# Solenoise_v4.net
KiCad netlist of a schematic drawn in EAGLE
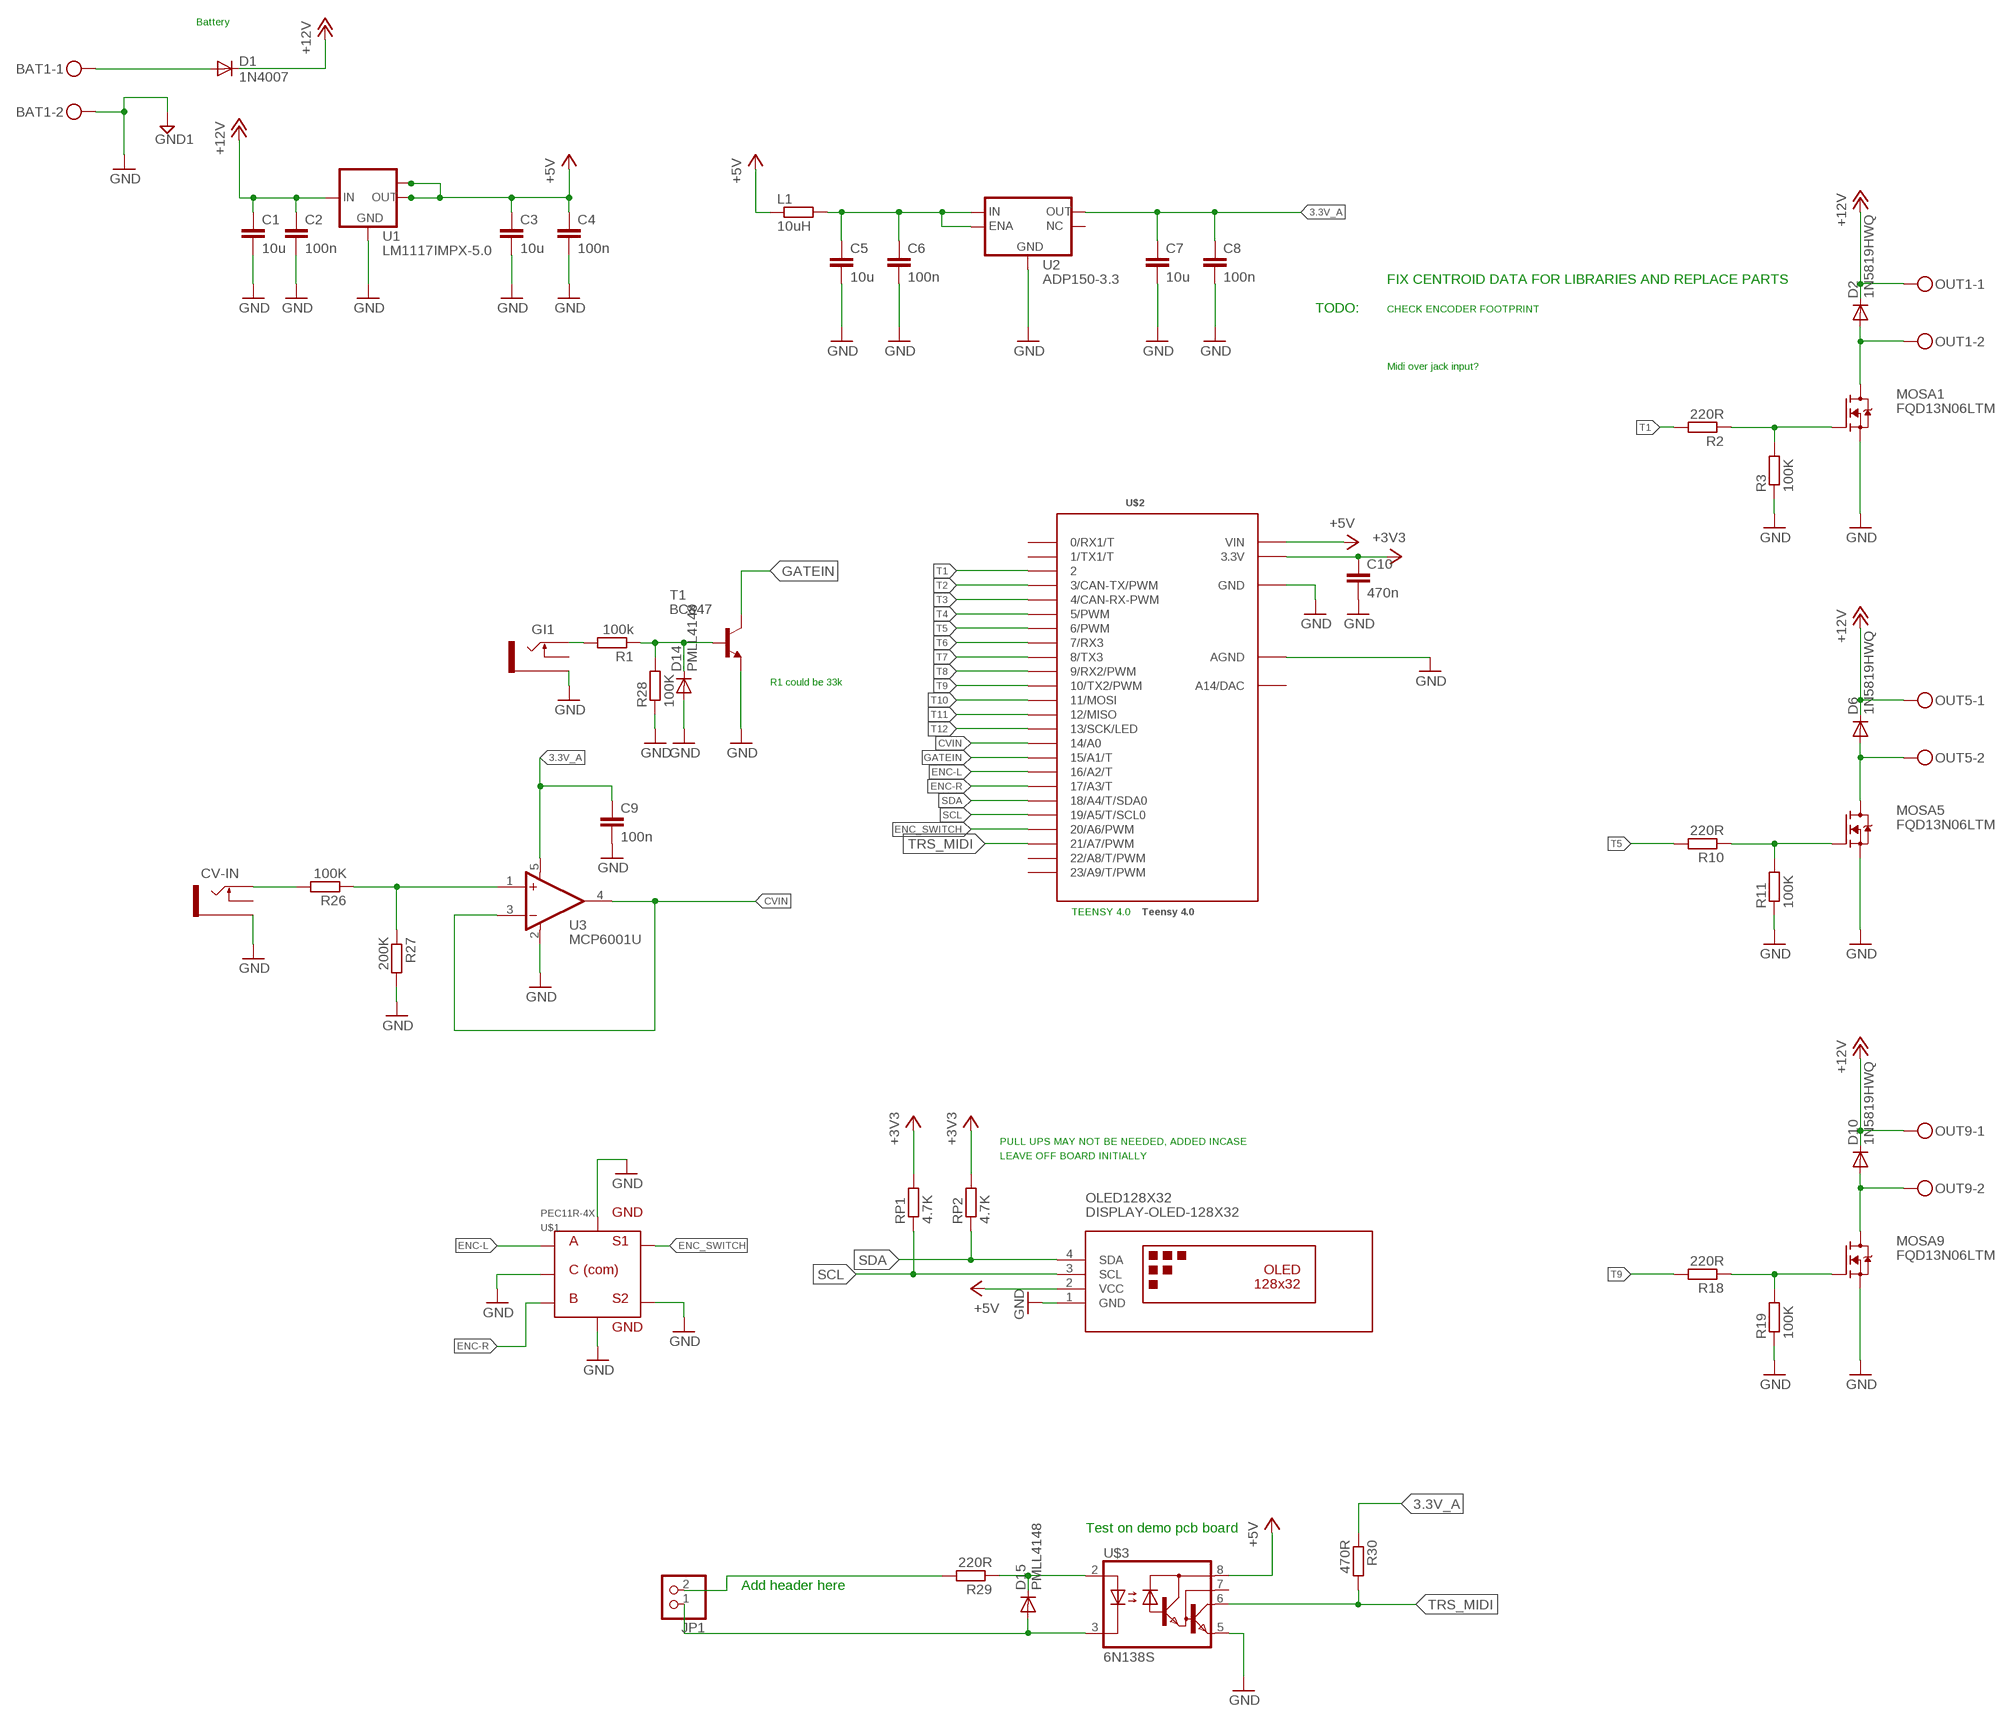
[diagram p0: schematic, sheet 1, part 1 of 2]
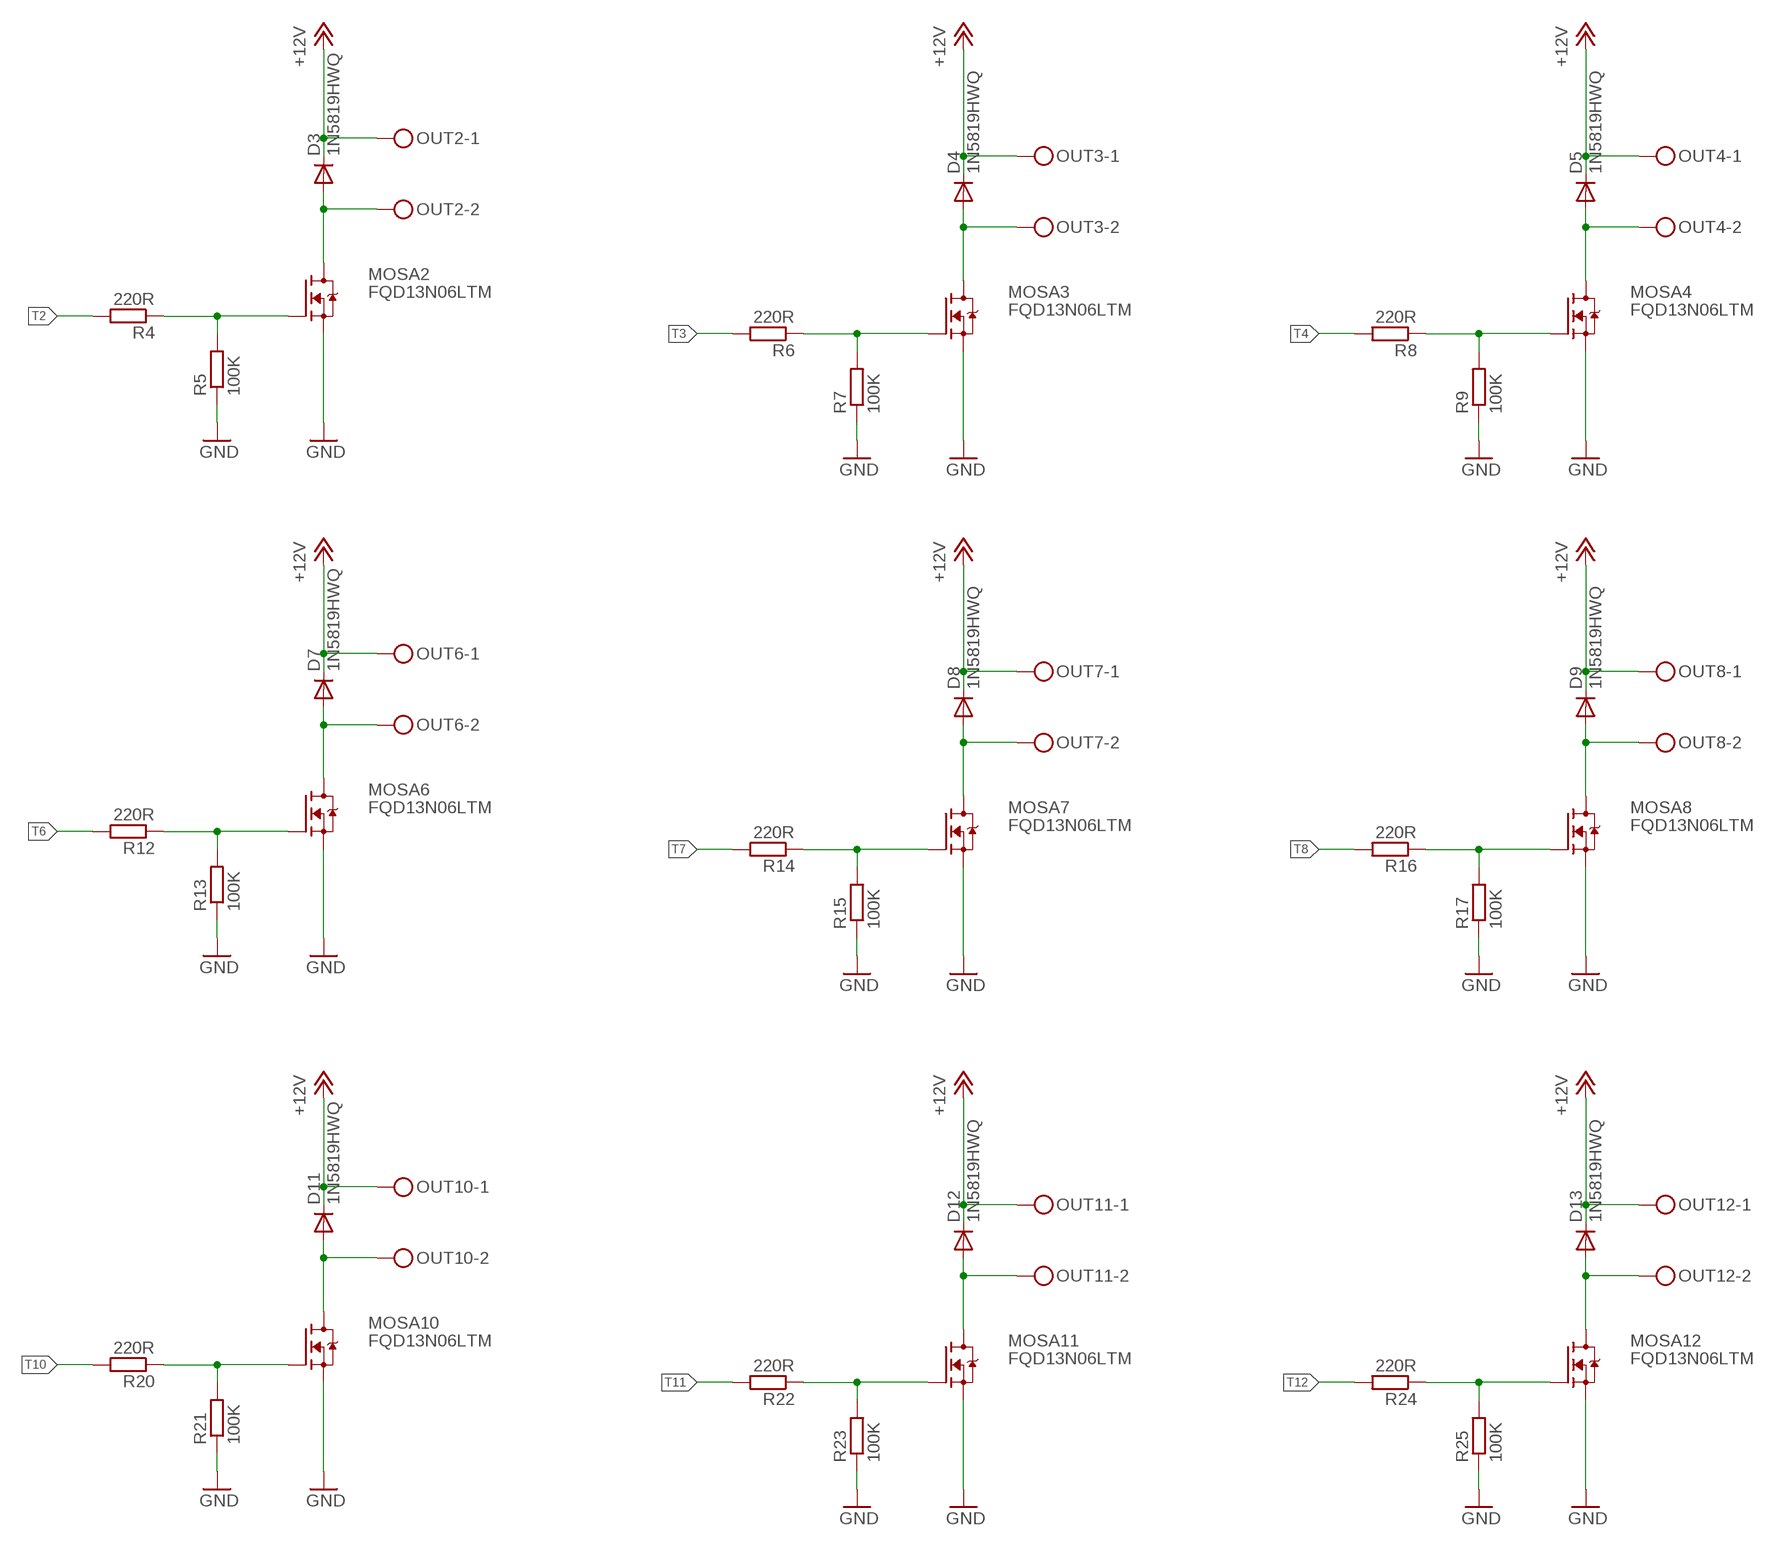
[diagram p1: schematic, sheet 1, part 2 of 2]

(export (version "E")
  (design (tool "Eeschema 10.0.6"))
  (components
    (comp (ref "BAT1")
      (value "MKDSN1,5/2-5,08")
      (footprint "eagle-import:MKDSN1,5_2-5,08")
      (fields (field (name "MPN") "MKDSN 1,5/2-5.08"))
      (libsource (lib "eagle-import") (part "MKDSN1,5/2-5,08"))
    )
    (comp (ref "C1")
      (value "10u")
      (footprint "eagle-import:C1206")
      (libsource (lib "eagle-import") (part "C-EUC1206"))
    )
    (comp (ref "C2")
      (value "100n")
      (footprint "eagle-import:C0805")
      (libsource (lib "eagle-import") (part "C-EUC0805"))
    )
    (comp (ref "C3")
      (value "10u")
      (footprint "eagle-import:C1206")
      (libsource (lib "eagle-import") (part "C-EUC1206"))
    )
    (comp (ref "C4")
      (value "100n")
      (footprint "eagle-import:C0805")
      (libsource (lib "eagle-import") (part "C-EUC0805"))
    )
    (comp (ref "C5")
      (value "10u")
      (footprint "eagle-import:C1206")
      (libsource (lib "eagle-import") (part "C-EUC1206"))
    )
    (comp (ref "C6")
      (value "100n")
      (footprint "eagle-import:C0805")
      (libsource (lib "eagle-import") (part "C-EUC0805"))
    )
    (comp (ref "C7")
      (value "10u")
      (footprint "eagle-import:C1206")
      (libsource (lib "eagle-import") (part "C-EUC1206"))
    )
    (comp (ref "C8")
      (value "100n")
      (footprint "eagle-import:C0805")
      (libsource (lib "eagle-import") (part "C-EUC0805"))
    )
    (comp (ref "C9")
      (value "100n")
      (footprint "eagle-import:C0805")
      (libsource (lib "eagle-import") (part "C-EUC0805"))
    )
    (comp (ref "C10")
      (value "470n")
      (footprint "eagle-import:C0805")
      (libsource (lib "eagle-import") (part "C-EUC0805"))
    )
    (comp (ref "CV-IN")
      (value "THONKICONNNEW")
      (footprint "eagle-import:WQP-PJ301M-12_JACK")
      (libsource (lib "eagle-import") (part "THONKICONNNEW"))
    )
    (comp (ref "D1")
      (value "1N4007")
      (footprint "eagle-import:DO41-10")
      (libsource (lib "eagle-import") (part "1N4004"))
    )
    (comp (ref "D2")
      (value "1N5819HWQ")
      (footprint "eagle-import:SOD123")
      (libsource (lib "eagle-import") (part "MBR0520LT"))
    )
    (comp (ref "D3")
      (value "1N5819HWQ")
      (footprint "eagle-import:SOD123")
      (libsource (lib "eagle-import") (part "MBR0520LT"))
    )
    (comp (ref "D4")
      (value "1N5819HWQ")
      (footprint "eagle-import:SOD123")
      (libsource (lib "eagle-import") (part "MBR0520LT"))
    )
    (comp (ref "D5")
      (value "1N5819HWQ")
      (footprint "eagle-import:SOD123")
      (libsource (lib "eagle-import") (part "MBR0520LT"))
    )
    (comp (ref "D6")
      (value "1N5819HWQ")
      (footprint "eagle-import:SOD123")
      (libsource (lib "eagle-import") (part "MBR0520LT"))
    )
    (comp (ref "D7")
      (value "1N5819HWQ")
      (footprint "eagle-import:SOD123")
      (libsource (lib "eagle-import") (part "MBR0520LT"))
    )
    (comp (ref "D8")
      (value "1N5819HWQ")
      (footprint "eagle-import:SOD123")
      (libsource (lib "eagle-import") (part "MBR0520LT"))
    )
    (comp (ref "D9")
      (value "1N5819HWQ")
      (footprint "eagle-import:SOD123")
      (libsource (lib "eagle-import") (part "MBR0520LT"))
    )
    (comp (ref "D10")
      (value "1N5819HWQ")
      (footprint "eagle-import:SOD123")
      (libsource (lib "eagle-import") (part "MBR0520LT"))
    )
    (comp (ref "D11")
      (value "1N5819HWQ")
      (footprint "eagle-import:SOD123")
      (libsource (lib "eagle-import") (part "MBR0520LT"))
    )
    (comp (ref "D12")
      (value "1N5819HWQ")
      (footprint "eagle-import:SOD123")
      (libsource (lib "eagle-import") (part "MBR0520LT"))
    )
    (comp (ref "D13")
      (value "1N5819HWQ")
      (footprint "eagle-import:SOD123")
      (libsource (lib "eagle-import") (part "MBR0520LT"))
    )
    (comp (ref "D14")
      (value "PMLL4148")
      (footprint "eagle-import:SOD80C")
      (libsource (lib "eagle-import") (part "PMLL4150"))
    )
    (comp (ref "D15")
      (value "PMLL4148")
      (footprint "eagle-import:SOD80C")
      (libsource (lib "eagle-import") (part "PMLL4150"))
    )
    (comp (ref "GI1")
      (value "THONKICONNNEW")
      (footprint "eagle-import:WQP-PJ301M-12_JACK")
      (libsource (lib "eagle-import") (part "THONKICONNNEW"))
    )
    (comp (ref "JP1")
      (value "PINHD-1X2")
      (footprint "eagle-import:1X02")
      (libsource (lib "eagle-import") (part "PINHD-1X2"))
    )
    (comp (ref "L1")
      (value "10uH")
      (footprint "eagle-import:R0805")
      (libsource (lib "eagle-import") (part "R-EU_R0805"))
    )
    (comp (ref "MOSA1")
      (value "FQD13N06LTM")
      (footprint "eagle-import:FQD13N06LTM")
      (libsource (lib "eagle-import") (part "FQD13N06LTM"))
    )
    (comp (ref "MOSA2")
      (value "FQD13N06LTM")
      (footprint "eagle-import:FQD13N06LTM")
      (libsource (lib "eagle-import") (part "FQD13N06LTM"))
    )
    (comp (ref "MOSA3")
      (value "FQD13N06LTM")
      (footprint "eagle-import:FQD13N06LTM")
      (libsource (lib "eagle-import") (part "FQD13N06LTM"))
    )
    (comp (ref "MOSA4")
      (value "FQD13N06LTM")
      (footprint "eagle-import:FQD13N06LTM")
      (libsource (lib "eagle-import") (part "FQD13N06LTM"))
    )
    (comp (ref "MOSA5")
      (value "FQD13N06LTM")
      (footprint "eagle-import:FQD13N06LTM")
      (libsource (lib "eagle-import") (part "FQD13N06LTM"))
    )
    (comp (ref "MOSA6")
      (value "FQD13N06LTM")
      (footprint "eagle-import:FQD13N06LTM")
      (libsource (lib "eagle-import") (part "FQD13N06LTM"))
    )
    (comp (ref "MOSA7")
      (value "FQD13N06LTM")
      (footprint "eagle-import:FQD13N06LTM")
      (libsource (lib "eagle-import") (part "FQD13N06LTM"))
    )
    (comp (ref "MOSA8")
      (value "FQD13N06LTM")
      (footprint "eagle-import:FQD13N06LTM")
      (libsource (lib "eagle-import") (part "FQD13N06LTM"))
    )
    (comp (ref "MOSA9")
      (value "FQD13N06LTM")
      (footprint "eagle-import:FQD13N06LTM")
      (libsource (lib "eagle-import") (part "FQD13N06LTM"))
    )
    (comp (ref "MOSA10")
      (value "FQD13N06LTM")
      (footprint "eagle-import:FQD13N06LTM")
      (libsource (lib "eagle-import") (part "FQD13N06LTM"))
    )
    (comp (ref "MOSA11")
      (value "FQD13N06LTM")
      (footprint "eagle-import:FQD13N06LTM")
      (libsource (lib "eagle-import") (part "FQD13N06LTM"))
    )
    (comp (ref "MOSA12")
      (value "FQD13N06LTM")
      (footprint "eagle-import:FQD13N06LTM")
      (libsource (lib "eagle-import") (part "FQD13N06LTM"))
    )
    (comp (ref "OLED128X32")
      (value "DISPLAY-OLED-128X32")
      (footprint "eagle-import:DISPLAY-OLED-128X32")
      (libsource (lib "eagle-import") (part "DISPLAY-OLED-128X32"))
    )
    (comp (ref "OUT1")
      (value "MKDSN1,5/2-5,08")
      (footprint "eagle-import:MKDSN1,5_2-5,08")
      (fields (field (name "MPN") "MKDSN 1,5/2-5.08"))
      (libsource (lib "eagle-import") (part "MKDSN1,5/2-5,08"))
    )
    (comp (ref "OUT2")
      (value "MKDSN1,5/2-5,08")
      (footprint "eagle-import:MKDSN1,5_2-5,08")
      (fields (field (name "MPN") "MKDSN 1,5/2-5.08"))
      (libsource (lib "eagle-import") (part "MKDSN1,5/2-5,08"))
    )
    (comp (ref "OUT3")
      (value "MKDSN1,5/2-5,08")
      (footprint "eagle-import:MKDSN1,5_2-5,08")
      (fields (field (name "MPN") "MKDSN 1,5/2-5.08"))
      (libsource (lib "eagle-import") (part "MKDSN1,5/2-5,08"))
    )
    (comp (ref "OUT4")
      (value "MKDSN1,5/2-5,08")
      (footprint "eagle-import:MKDSN1,5_2-5,08")
      (fields (field (name "MPN") "MKDSN 1,5/2-5.08"))
      (libsource (lib "eagle-import") (part "MKDSN1,5/2-5,08"))
    )
    (comp (ref "OUT5")
      (value "MKDSN1,5/2-5,08")
      (footprint "eagle-import:MKDSN1,5_2-5,08")
      (fields (field (name "MPN") "MKDSN 1,5/2-5.08"))
      (libsource (lib "eagle-import") (part "MKDSN1,5/2-5,08"))
    )
    (comp (ref "OUT6")
      (value "MKDSN1,5/2-5,08")
      (footprint "eagle-import:MKDSN1,5_2-5,08")
      (fields (field (name "MPN") "MKDSN 1,5/2-5.08"))
      (libsource (lib "eagle-import") (part "MKDSN1,5/2-5,08"))
    )
    (comp (ref "OUT7")
      (value "MKDSN1,5/2-5,08")
      (footprint "eagle-import:MKDSN1,5_2-5,08")
      (fields (field (name "MPN") "MKDSN 1,5/2-5.08"))
      (libsource (lib "eagle-import") (part "MKDSN1,5/2-5,08"))
    )
    (comp (ref "OUT8")
      (value "MKDSN1,5/2-5,08")
      (footprint "eagle-import:MKDSN1,5_2-5,08")
      (fields (field (name "MPN") "MKDSN 1,5/2-5.08"))
      (libsource (lib "eagle-import") (part "MKDSN1,5/2-5,08"))
    )
    (comp (ref "OUT9")
      (value "MKDSN1,5/2-5,08")
      (footprint "eagle-import:MKDSN1,5_2-5,08")
      (fields (field (name "MPN") "MKDSN 1,5/2-5.08"))
      (libsource (lib "eagle-import") (part "MKDSN1,5/2-5,08"))
    )
    (comp (ref "OUT10")
      (value "MKDSN1,5/2-5,08")
      (footprint "eagle-import:MKDSN1,5_2-5,08")
      (fields (field (name "MPN") "MKDSN 1,5/2-5.08"))
      (libsource (lib "eagle-import") (part "MKDSN1,5/2-5,08"))
    )
    (comp (ref "OUT11")
      (value "MKDSN1,5/2-5,08")
      (footprint "eagle-import:MKDSN1,5_2-5,08")
      (fields (field (name "MPN") "MKDSN 1,5/2-5.08"))
      (libsource (lib "eagle-import") (part "MKDSN1,5/2-5,08"))
    )
    (comp (ref "OUT12")
      (value "MKDSN1,5/2-5,08")
      (footprint "eagle-import:MKDSN1,5_2-5,08")
      (fields (field (name "MPN") "MKDSN 1,5/2-5.08"))
      (libsource (lib "eagle-import") (part "MKDSN1,5/2-5,08"))
    )
    (comp (ref "R1")
      (value "100k")
      (footprint "eagle-import:R0805")
      (libsource (lib "eagle-import") (part "R-EU_R0805"))
    )
    (comp (ref "R2")
      (value "220R")
      (footprint "eagle-import:R0805")
      (libsource (lib "eagle-import") (part "R-EU_R0805"))
    )
    (comp (ref "R3")
      (value "100K")
      (footprint "eagle-import:R0805")
      (libsource (lib "eagle-import") (part "R-EU_R0805"))
    )
    (comp (ref "R4")
      (value "220R")
      (footprint "eagle-import:R0805")
      (libsource (lib "eagle-import") (part "R-EU_R0805"))
    )
    (comp (ref "R5")
      (value "100K")
      (footprint "eagle-import:R0805")
      (libsource (lib "eagle-import") (part "R-EU_R0805"))
    )
    (comp (ref "R6")
      (value "220R")
      (footprint "eagle-import:R0805")
      (libsource (lib "eagle-import") (part "R-EU_R0805"))
    )
    (comp (ref "R7")
      (value "100K")
      (footprint "eagle-import:R0805")
      (libsource (lib "eagle-import") (part "R-EU_R0805"))
    )
    (comp (ref "R8")
      (value "220R")
      (footprint "eagle-import:R0805")
      (libsource (lib "eagle-import") (part "R-EU_R0805"))
    )
    (comp (ref "R9")
      (value "100K")
      (footprint "eagle-import:R0805")
      (libsource (lib "eagle-import") (part "R-EU_R0805"))
    )
    (comp (ref "R10")
      (value "220R")
      (footprint "eagle-import:R0805")
      (libsource (lib "eagle-import") (part "R-EU_R0805"))
    )
    (comp (ref "R11")
      (value "100K")
      (footprint "eagle-import:R0805")
      (libsource (lib "eagle-import") (part "R-EU_R0805"))
    )
    (comp (ref "R12")
      (value "220R")
      (footprint "eagle-import:R0805")
      (libsource (lib "eagle-import") (part "R-EU_R0805"))
    )
    (comp (ref "R13")
      (value "100K")
      (footprint "eagle-import:R0805")
      (libsource (lib "eagle-import") (part "R-EU_R0805"))
    )
    (comp (ref "R14")
      (value "220R")
      (footprint "eagle-import:R0805")
      (libsource (lib "eagle-import") (part "R-EU_R0805"))
    )
    (comp (ref "R15")
      (value "100K")
      (footprint "eagle-import:R0805")
      (libsource (lib "eagle-import") (part "R-EU_R0805"))
    )
    (comp (ref "R16")
      (value "220R")
      (footprint "eagle-import:R0805")
      (libsource (lib "eagle-import") (part "R-EU_R0805"))
    )
    (comp (ref "R17")
      (value "100K")
      (footprint "eagle-import:R0805")
      (libsource (lib "eagle-import") (part "R-EU_R0805"))
    )
    (comp (ref "R18")
      (value "220R")
      (footprint "eagle-import:R0805")
      (libsource (lib "eagle-import") (part "R-EU_R0805"))
    )
    (comp (ref "R19")
      (value "100K")
      (footprint "eagle-import:R0805")
      (libsource (lib "eagle-import") (part "R-EU_R0805"))
    )
    (comp (ref "R20")
      (value "220R")
      (footprint "eagle-import:R0805")
      (libsource (lib "eagle-import") (part "R-EU_R0805"))
    )
    (comp (ref "R21")
      (value "100K")
      (footprint "eagle-import:R0805")
      (libsource (lib "eagle-import") (part "R-EU_R0805"))
    )
    (comp (ref "R22")
      (value "220R")
      (footprint "eagle-import:R0805")
      (libsource (lib "eagle-import") (part "R-EU_R0805"))
    )
    (comp (ref "R23")
      (value "100K")
      (footprint "eagle-import:R0805")
      (libsource (lib "eagle-import") (part "R-EU_R0805"))
    )
    (comp (ref "R24")
      (value "220R")
      (footprint "eagle-import:R0805")
      (libsource (lib "eagle-import") (part "R-EU_R0805"))
    )
    (comp (ref "R25")
      (value "100K")
      (footprint "eagle-import:R0805")
      (libsource (lib "eagle-import") (part "R-EU_R0805"))
    )
    (comp (ref "R26")
      (value "100K")
      (footprint "eagle-import:R0805")
      (libsource (lib "eagle-import") (part "R-EU_R0805"))
    )
    (comp (ref "R27")
      (value "200K")
      (footprint "eagle-import:R0805")
      (libsource (lib "eagle-import") (part "R-EU_R0805"))
    )
    (comp (ref "R28")
      (value "100K")
      (footprint "eagle-import:R0805")
      (libsource (lib "eagle-import") (part "R-EU_R0805"))
    )
    (comp (ref "R29")
      (value "220R")
      (footprint "eagle-import:R0805")
      (libsource (lib "eagle-import") (part "R-EU_R0805"))
    )
    (comp (ref "R30")
      (value "470R")
      (footprint "eagle-import:R0805")
      (libsource (lib "eagle-import") (part "R-EU_R0805"))
    )
    (comp (ref "RP1")
      (value "4.7K")
      (footprint "eagle-import:R0805")
      (libsource (lib "eagle-import") (part "R-EU_R0805"))
    )
    (comp (ref "RP2")
      (value "4.7K")
      (footprint "eagle-import:R0805")
      (libsource (lib "eagle-import") (part "R-EU_R0805"))
    )
    (comp (ref "T1")
      (value "BC847")
      (footprint "eagle-import:SOT23")
      (libsource (lib "eagle-import") (part "BC847"))
    )
    (comp (ref "U$1")
      (value "PEC11R-4X")
      (footprint "eagle-import:ENC")
      (libsource (lib "eagle-import") (part "PEC11R-4X"))
    )
    (comp (ref "U$2")
      (value "Teensy 4.0")
      (footprint "eagle-import:TEENSY_3.1_DAC")
      (libsource (lib "eagle-import") (part "TEENSY_3.1_DAC"))
    )
    (comp (ref "U$3")
      (value "6N138S")
      (footprint "eagle-import:6N138S")
      (libsource (lib "eagle-import") (part "6N138S"))
    )
    (comp (ref "U1")
      (value "LM1117IMPX-5.0")
      (footprint "eagle-import:SOT223")
      (libsource (lib "eagle-import") (part "LM1117IMPX-5.0"))
    )
    (comp (ref "U2")
      (value "ADP150-3.3")
      (footprint "eagle-import:SOT23-5")
      (libsource (lib "eagle-import") (part "ADP150-3.3"))
    )
    (comp (ref "U3")
      (value "MCP6001U")
      (footprint "eagle-import:MCP6001")
      (libsource (lib "eagle-import") (part "MCP6001U"))
    )
  )
  (nets
    (net (code "1") (name "+3V3") (class "Default")
      (node (ref "C10") (pin "1") (pinfunction "1_1") (pintype "passive"))
      (node (ref "RP1") (pin "2") (pinfunction "2_2") (pintype "passive"))
      (node (ref "RP2") (pin "2") (pinfunction "2_2") (pintype "passive"))
      (node (ref "U$2") (pin "3.3V") (pinfunction "3.3V_3.3V") (pintype "power_in"))
    )
    (net (code "2") (name "+5V") (class "Default")
      (node (ref "C3") (pin "1") (pinfunction "1_1") (pintype "passive"))
      (node (ref "C4") (pin "1") (pinfunction "1_1") (pintype "passive"))
      (node (ref "L1") (pin "1") (pinfunction "1_1") (pintype "passive"))
      (node (ref "OLED128X32") (pin "2") (pinfunction "VCC_2") (pintype "power_in"))
      (node (ref "U$2") (pin "VIN") (pinfunction "VIN_VIN") (pintype "power_in"))
      (node (ref "U$3") (pin "8") (pinfunction "VCC_8") (pintype "passive"))
      (node (ref "U1") (pin "2") (pinfunction "OUT_2") (pintype "passive"))
      (node (ref "U1") (pin "TAB") (pinfunction "OUT1_TAB") (pintype "passive"))
    )
    (net (code "3") (name "+12V") (class "Default")
      (node (ref "C1") (pin "1") (pinfunction "1_1") (pintype "passive"))
      (node (ref "C2") (pin "1") (pinfunction "1_1") (pintype "passive"))
      (node (ref "D1") (pin "C") (pinfunction "C_C") (pintype "passive"))
      (node (ref "D10") (pin "C") (pinfunction "C_C") (pintype "passive"))
      (node (ref "D11") (pin "C") (pinfunction "C_C") (pintype "passive"))
      (node (ref "D12") (pin "C") (pinfunction "C_C") (pintype "passive"))
      (node (ref "D13") (pin "C") (pinfunction "C_C") (pintype "passive"))
      (node (ref "D2") (pin "C") (pinfunction "C_C") (pintype "passive"))
      (node (ref "D3") (pin "C") (pinfunction "C_C") (pintype "passive"))
      (node (ref "D4") (pin "C") (pinfunction "C_C") (pintype "passive"))
      (node (ref "D5") (pin "C") (pinfunction "C_C") (pintype "passive"))
      (node (ref "D6") (pin "C") (pinfunction "C_C") (pintype "passive"))
      (node (ref "D7") (pin "C") (pinfunction "C_C") (pintype "passive"))
      (node (ref "D8") (pin "C") (pinfunction "C_C") (pintype "passive"))
      (node (ref "D9") (pin "C") (pinfunction "C_C") (pintype "passive"))
      (node (ref "OUT1") (pin "1") (pinfunction "KL_1") (pintype "passive"))
      (node (ref "OUT10") (pin "1") (pinfunction "KL_1") (pintype "passive"))
      (node (ref "OUT11") (pin "1") (pinfunction "KL_1") (pintype "passive"))
      (node (ref "OUT12") (pin "1") (pinfunction "KL_1") (pintype "passive"))
      (node (ref "OUT2") (pin "1") (pinfunction "KL_1") (pintype "passive"))
      (node (ref "OUT3") (pin "1") (pinfunction "KL_1") (pintype "passive"))
      (node (ref "OUT4") (pin "1") (pinfunction "KL_1") (pintype "passive"))
      (node (ref "OUT5") (pin "1") (pinfunction "KL_1") (pintype "passive"))
      (node (ref "OUT6") (pin "1") (pinfunction "KL_1") (pintype "passive"))
      (node (ref "OUT7") (pin "1") (pinfunction "KL_1") (pintype "passive"))
      (node (ref "OUT8") (pin "1") (pinfunction "KL_1") (pintype "passive"))
      (node (ref "OUT9") (pin "1") (pinfunction "KL_1") (pintype "passive"))
      (node (ref "U1") (pin "3") (pinfunction "IN_3") (pintype "input"))
    )
    (net (code "4") (name "3.3V_A") (class "Default")
      (node (ref "C7") (pin "1") (pinfunction "1_1") (pintype "passive"))
      (node (ref "C8") (pin "1") (pinfunction "1_1") (pintype "passive"))
      (node (ref "C9") (pin "1") (pinfunction "1_1") (pintype "passive"))
      (node (ref "R30") (pin "1") (pinfunction "1_1") (pintype "passive"))
      (node (ref "U2") (pin "OUT") (pinfunction "VOUT_OUT") (pintype "passive"))
      (node (ref "U3") (pin "5") (pinfunction "V+_5") (pintype "power_in"))
    )
    (net (code "5") (name "CVIN") (class "Default")
      (node (ref "U$2") (pin "14/A0") (pinfunction "14/A0_14/A0") (pintype "bidirectional"))
      (node (ref "U3") (pin "3") (pinfunction "-IN_3") (pintype "input"))
      (node (ref "U3") (pin "4") (pinfunction "OUT_4") (pintype "output"))
    )
    (net (code "6") (name "ENC-L") (class "Default")
      (node (ref "U$1") (pin "A") (pinfunction "A_A") (pintype "passive"))
      (node (ref "U$2") (pin "16/A2") (pinfunction "16/A2/T_16/A2") (pintype "bidirectional"))
    )
    (net (code "7") (name "ENC-R") (class "Default")
      (node (ref "U$1") (pin "B") (pinfunction "B_B") (pintype "passive"))
      (node (ref "U$2") (pin "17/A3") (pinfunction "17/A3/T_17/A3") (pintype "bidirectional"))
    )
    (net (code "8") (name "ENC_SWITCH") (class "Default")
      (node (ref "U$1") (pin "1") (pinfunction "SW1_1") (pintype "passive"))
      (node (ref "U$2") (pin "20/A6") (pinfunction "20/A6/PWM_20/A6") (pintype "bidirectional"))
    )
    (net (code "9") (name "GATEIN") (class "Default")
      (node (ref "T1") (pin "3") (pinfunction "C_3") (pintype "passive"))
      (node (ref "U$2") (pin "15/A1") (pinfunction "15/A1/T_15/A1") (pintype "bidirectional"))
    )
    (net (code "10") (name "GND") (class "Default")
      (node (ref "BAT1") (pin "2") (pinfunction "KL_2") (pintype "passive"))
      (node (ref "C1") (pin "2") (pinfunction "2_2") (pintype "passive"))
      (node (ref "C10") (pin "2") (pinfunction "2_2") (pintype "passive"))
      (node (ref "C2") (pin "2") (pinfunction "2_2") (pintype "passive"))
      (node (ref "C3") (pin "2") (pinfunction "2_2") (pintype "passive"))
      (node (ref "C4") (pin "2") (pinfunction "2_2") (pintype "passive"))
      (node (ref "C5") (pin "2") (pinfunction "2_2") (pintype "passive"))
      (node (ref "C6") (pin "2") (pinfunction "2_2") (pintype "passive"))
      (node (ref "C7") (pin "2") (pinfunction "2_2") (pintype "passive"))
      (node (ref "C8") (pin "2") (pinfunction "2_2") (pintype "passive"))
      (node (ref "C9") (pin "2") (pinfunction "2_2") (pintype "passive"))
      (node (ref "CV-IN") (pin "P$3_SLEEVE") (pinfunction "SLEEVE_P$3_SLEEVE") (pintype "passive"))
      (node (ref "D14") (pin "A") (pinfunction "A_A") (pintype "passive"))
      (node (ref "GI1") (pin "P$3_SLEEVE") (pinfunction "SLEEVE_P$3_SLEEVE") (pintype "passive"))
      (node (ref "MOSA1") (pin "2") (pinfunction "S_2") (pintype "passive"))
      (node (ref "MOSA10") (pin "2") (pinfunction "S_2") (pintype "passive"))
      (node (ref "MOSA11") (pin "2") (pinfunction "S_2") (pintype "passive"))
      (node (ref "MOSA12") (pin "2") (pinfunction "S_2") (pintype "passive"))
      (node (ref "MOSA2") (pin "2") (pinfunction "S_2") (pintype "passive"))
      (node (ref "MOSA3") (pin "2") (pinfunction "S_2") (pintype "passive"))
      (node (ref "MOSA4") (pin "2") (pinfunction "S_2") (pintype "passive"))
      (node (ref "MOSA5") (pin "2") (pinfunction "S_2") (pintype "passive"))
      (node (ref "MOSA6") (pin "2") (pinfunction "S_2") (pintype "passive"))
      (node (ref "MOSA7") (pin "2") (pinfunction "S_2") (pintype "passive"))
      (node (ref "MOSA8") (pin "2") (pinfunction "S_2") (pintype "passive"))
      (node (ref "MOSA9") (pin "2") (pinfunction "S_2") (pintype "passive"))
      (node (ref "OLED128X32") (pin "1") (pinfunction "GND_1") (pintype "power_in"))
      (node (ref "R11") (pin "1") (pinfunction "1_1") (pintype "passive"))
      (node (ref "R13") (pin "1") (pinfunction "1_1") (pintype "passive"))
      (node (ref "R15") (pin "1") (pinfunction "1_1") (pintype "passive"))
      (node (ref "R17") (pin "1") (pinfunction "1_1") (pintype "passive"))
      (node (ref "R19") (pin "1") (pinfunction "1_1") (pintype "passive"))
      (node (ref "R21") (pin "1") (pinfunction "1_1") (pintype "passive"))
      (node (ref "R23") (pin "1") (pinfunction "1_1") (pintype "passive"))
      (node (ref "R25") (pin "1") (pinfunction "1_1") (pintype "passive"))
      (node (ref "R27") (pin "2") (pinfunction "2_2") (pintype "passive"))
      (node (ref "R28") (pin "1") (pinfunction "1_1") (pintype "passive"))
      (node (ref "R3") (pin "1") (pinfunction "1_1") (pintype "passive"))
      (node (ref "R5") (pin "1") (pinfunction "1_1") (pintype "passive"))
      (node (ref "R7") (pin "1") (pinfunction "1_1") (pintype "passive"))
      (node (ref "R9") (pin "1") (pinfunction "1_1") (pintype "passive"))
      (node (ref "T1") (pin "2") (pinfunction "E_2") (pintype "passive"))
      (node (ref "U$1") (pin "2") (pinfunction "SW2_2") (pintype "passive"))
      (node (ref "U$1") (pin "C") (pinfunction "C_C") (pintype "passive"))
      (node (ref "U$1") (pin "GND1") (pinfunction "GND1_GND1") (pintype "passive"))
      (node (ref "U$1") (pin "GND2") (pinfunction "GND2_GND2") (pintype "passive"))
      (node (ref "U$2") (pin "AGND") (pinfunction "AGND_AGND") (pintype "power_in"))
      (node (ref "U$2") (pin "GND") (pinfunction "GND_GND") (pintype "power_in"))
      (node (ref "U$3") (pin "5") (pinfunction "GND_5") (pintype "passive"))
      (node (ref "U1") (pin "1") (pinfunction "GND_1") (pintype "input"))
      (node (ref "U2") (pin "GND") (pinfunction "GND_GND") (pintype "input"))
      (node (ref "U3") (pin "2") (pinfunction "V-_2") (pintype "power_in"))
    )
    (net (code "11") (name "Net-(BAT1A-KL)") (class "Default")
      (node (ref "BAT1") (pin "1") (pinfunction "KL_1") (pintype "passive"))
      (node (ref "D1") (pin "A") (pinfunction "A_A") (pintype "passive"))
    )
    (net (code "12") (name "Net-(CV-IN-TIP)") (class "Default")
      (node (ref "CV-IN") (pin "P$1_TIP") (pinfunction "TIP_P$1_TIP") (pintype "passive"))
      (node (ref "R26") (pin "2") (pinfunction "2_2") (pintype "passive"))
    )
    (net (code "13") (name "Net-(GI1-TIP)") (class "Default")
      (node (ref "GI1") (pin "P$1_TIP") (pinfunction "TIP_P$1_TIP") (pintype "passive"))
      (node (ref "R1") (pin "2") (pinfunction "2_2") (pintype "passive"))
    )
    (net (code "14") (name "Net-(JP1-Pad2)") (class "Default")
      (node (ref "JP1") (pin "2") (pinfunction "2_2") (pintype "passive"))
      (node (ref "R29") (pin "2") (pinfunction "2_2") (pintype "passive"))
    )
    (net (code "15") (name "Net-(MOSA1-D)") (class "Default")
      (node (ref "D2") (pin "A") (pinfunction "A_A") (pintype "passive"))
      (node (ref "MOSA1") (pin "3") (pinfunction "D_3") (pintype "passive"))
      (node (ref "OUT1") (pin "2") (pinfunction "KL_2") (pintype "passive"))
    )
    (net (code "16") (name "Net-(MOSA1-G)") (class "Default")
      (node (ref "MOSA1") (pin "1") (pinfunction "G_1") (pintype "passive"))
      (node (ref "R2") (pin "1") (pinfunction "1_1") (pintype "passive"))
      (node (ref "R3") (pin "2") (pinfunction "2_2") (pintype "passive"))
    )
    (net (code "17") (name "Net-(MOSA2-D)") (class "Default")
      (node (ref "D3") (pin "A") (pinfunction "A_A") (pintype "passive"))
      (node (ref "MOSA2") (pin "3") (pinfunction "D_3") (pintype "passive"))
      (node (ref "OUT2") (pin "2") (pinfunction "KL_2") (pintype "passive"))
    )
    (net (code "18") (name "Net-(MOSA2-G)") (class "Default")
      (node (ref "MOSA2") (pin "1") (pinfunction "G_1") (pintype "passive"))
      (node (ref "R4") (pin "1") (pinfunction "1_1") (pintype "passive"))
      (node (ref "R5") (pin "2") (pinfunction "2_2") (pintype "passive"))
    )
    (net (code "19") (name "Net-(MOSA3-D)") (class "Default")
      (node (ref "D4") (pin "A") (pinfunction "A_A") (pintype "passive"))
      (node (ref "MOSA3") (pin "3") (pinfunction "D_3") (pintype "passive"))
      (node (ref "OUT3") (pin "2") (pinfunction "KL_2") (pintype "passive"))
    )
    (net (code "20") (name "Net-(MOSA3-G)") (class "Default")
      (node (ref "MOSA3") (pin "1") (pinfunction "G_1") (pintype "passive"))
      (node (ref "R6") (pin "1") (pinfunction "1_1") (pintype "passive"))
      (node (ref "R7") (pin "2") (pinfunction "2_2") (pintype "passive"))
    )
    (net (code "21") (name "Net-(MOSA4-D)") (class "Default")
      (node (ref "D5") (pin "A") (pinfunction "A_A") (pintype "passive"))
      (node (ref "MOSA4") (pin "3") (pinfunction "D_3") (pintype "passive"))
      (node (ref "OUT4") (pin "2") (pinfunction "KL_2") (pintype "passive"))
    )
    (net (code "22") (name "Net-(MOSA4-G)") (class "Default")
      (node (ref "MOSA4") (pin "1") (pinfunction "G_1") (pintype "passive"))
      (node (ref "R8") (pin "1") (pinfunction "1_1") (pintype "passive"))
      (node (ref "R9") (pin "2") (pinfunction "2_2") (pintype "passive"))
    )
    (net (code "23") (name "Net-(MOSA5-D)") (class "Default")
      (node (ref "D6") (pin "A") (pinfunction "A_A") (pintype "passive"))
      (node (ref "MOSA5") (pin "3") (pinfunction "D_3") (pintype "passive"))
      (node (ref "OUT5") (pin "2") (pinfunction "KL_2") (pintype "passive"))
    )
    (net (code "24") (name "Net-(MOSA5-G)") (class "Default")
      (node (ref "MOSA5") (pin "1") (pinfunction "G_1") (pintype "passive"))
      (node (ref "R10") (pin "1") (pinfunction "1_1") (pintype "passive"))
      (node (ref "R11") (pin "2") (pinfunction "2_2") (pintype "passive"))
    )
    (net (code "25") (name "Net-(MOSA6-D)") (class "Default")
      (node (ref "D7") (pin "A") (pinfunction "A_A") (pintype "passive"))
      (node (ref "MOSA6") (pin "3") (pinfunction "D_3") (pintype "passive"))
      (node (ref "OUT6") (pin "2") (pinfunction "KL_2") (pintype "passive"))
    )
    (net (code "26") (name "Net-(MOSA6-G)") (class "Default")
      (node (ref "MOSA6") (pin "1") (pinfunction "G_1") (pintype "passive"))
      (node (ref "R12") (pin "1") (pinfunction "1_1") (pintype "passive"))
      (node (ref "R13") (pin "2") (pinfunction "2_2") (pintype "passive"))
    )
    (net (code "27") (name "Net-(MOSA7-D)") (class "Default")
      (node (ref "D8") (pin "A") (pinfunction "A_A") (pintype "passive"))
      (node (ref "MOSA7") (pin "3") (pinfunction "D_3") (pintype "passive"))
      (node (ref "OUT7") (pin "2") (pinfunction "KL_2") (pintype "passive"))
    )
    (net (code "28") (name "Net-(MOSA7-G)") (class "Default")
      (node (ref "MOSA7") (pin "1") (pinfunction "G_1") (pintype "passive"))
      (node (ref "R14") (pin "1") (pinfunction "1_1") (pintype "passive"))
      (node (ref "R15") (pin "2") (pinfunction "2_2") (pintype "passive"))
    )
    (net (code "29") (name "Net-(MOSA8-D)") (class "Default")
      (node (ref "D9") (pin "A") (pinfunction "A_A") (pintype "passive"))
      (node (ref "MOSA8") (pin "3") (pinfunction "D_3") (pintype "passive"))
      (node (ref "OUT8") (pin "2") (pinfunction "KL_2") (pintype "passive"))
    )
    (net (code "30") (name "Net-(MOSA8-G)") (class "Default")
      (node (ref "MOSA8") (pin "1") (pinfunction "G_1") (pintype "passive"))
      (node (ref "R16") (pin "1") (pinfunction "1_1") (pintype "passive"))
      (node (ref "R17") (pin "2") (pinfunction "2_2") (pintype "passive"))
    )
    (net (code "31") (name "Net-(MOSA9-D)") (class "Default")
      (node (ref "D10") (pin "A") (pinfunction "A_A") (pintype "passive"))
      (node (ref "MOSA9") (pin "3") (pinfunction "D_3") (pintype "passive"))
      (node (ref "OUT9") (pin "2") (pinfunction "KL_2") (pintype "passive"))
    )
    (net (code "32") (name "Net-(MOSA9-G)") (class "Default")
      (node (ref "MOSA9") (pin "1") (pinfunction "G_1") (pintype "passive"))
      (node (ref "R18") (pin "1") (pinfunction "1_1") (pintype "passive"))
      (node (ref "R19") (pin "2") (pinfunction "2_2") (pintype "passive"))
    )
    (net (code "33") (name "Net-(MOSA10-D)") (class "Default")
      (node (ref "D11") (pin "A") (pinfunction "A_A") (pintype "passive"))
      (node (ref "MOSA10") (pin "3") (pinfunction "D_3") (pintype "passive"))
      (node (ref "OUT10") (pin "2") (pinfunction "KL_2") (pintype "passive"))
    )
    (net (code "34") (name "Net-(MOSA10-G)") (class "Default")
      (node (ref "MOSA10") (pin "1") (pinfunction "G_1") (pintype "passive"))
      (node (ref "R20") (pin "1") (pinfunction "1_1") (pintype "passive"))
      (node (ref "R21") (pin "2") (pinfunction "2_2") (pintype "passive"))
    )
    (net (code "35") (name "Net-(MOSA11-D)") (class "Default")
      (node (ref "D12") (pin "A") (pinfunction "A_A") (pintype "passive"))
      (node (ref "MOSA11") (pin "3") (pinfunction "D_3") (pintype "passive"))
      (node (ref "OUT11") (pin "2") (pinfunction "KL_2") (pintype "passive"))
    )
    (net (code "36") (name "Net-(MOSA11-G)") (class "Default")
      (node (ref "MOSA11") (pin "1") (pinfunction "G_1") (pintype "passive"))
      (node (ref "R22") (pin "1") (pinfunction "1_1") (pintype "passive"))
      (node (ref "R23") (pin "2") (pinfunction "2_2") (pintype "passive"))
    )
    (net (code "37") (name "Net-(MOSA12-D)") (class "Default")
      (node (ref "D13") (pin "A") (pinfunction "A_A") (pintype "passive"))
      (node (ref "MOSA12") (pin "3") (pinfunction "D_3") (pintype "passive"))
      (node (ref "OUT12") (pin "2") (pinfunction "KL_2") (pintype "passive"))
    )
    (net (code "38") (name "Net-(MOSA12-G)") (class "Default")
      (node (ref "MOSA12") (pin "1") (pinfunction "G_1") (pintype "passive"))
      (node (ref "R24") (pin "1") (pinfunction "1_1") (pintype "passive"))
      (node (ref "R25") (pin "2") (pinfunction "2_2") (pintype "passive"))
    )
    (net (code "39") (name "Net-(T1-B)") (class "Default")
      (node (ref "D14") (pin "C") (pinfunction "C_C") (pintype "passive"))
      (node (ref "R1") (pin "1") (pinfunction "1_1") (pintype "passive"))
      (node (ref "R28") (pin "2") (pinfunction "2_2") (pintype "passive"))
      (node (ref "T1") (pin "1") (pinfunction "B_1") (pintype "passive"))
    )
    (net (code "40") (name "Net-(U$3-A)") (class "Default")
      (node (ref "D15") (pin "C") (pinfunction "C_C") (pintype "passive"))
      (node (ref "R29") (pin "1") (pinfunction "1_1") (pintype "passive"))
      (node (ref "U$3") (pin "2") (pinfunction "A_2") (pintype "passive"))
    )
    (net (code "41") (name "Net-(U$3-C)") (class "Default")
      (node (ref "D15") (pin "A") (pinfunction "A_A") (pintype "passive"))
      (node (ref "JP1") (pin "1") (pinfunction "1_1") (pintype "passive"))
      (node (ref "U$3") (pin "3") (pinfunction "C_3") (pintype "passive"))
    )
    (net (code "42") (name "Net-(U2-ENA)") (class "Default")
      (node (ref "C5") (pin "1") (pinfunction "1_1") (pintype "passive"))
      (node (ref "C6") (pin "1") (pinfunction "1_1") (pintype "passive"))
      (node (ref "L1") (pin "2") (pinfunction "2_2") (pintype "passive"))
      (node (ref "U2") (pin "EN") (pinfunction "ENA_EN") (pintype "input"))
      (node (ref "U2") (pin "VIN") (pinfunction "IN_VIN") (pintype "input"))
    )
    (net (code "43") (name "Net-(U3-+IN)") (class "Default")
      (node (ref "R26") (pin "1") (pinfunction "1_1") (pintype "passive"))
      (node (ref "R27") (pin "1") (pinfunction "1_1") (pintype "passive"))
      (node (ref "U3") (pin "1") (pinfunction "+IN_1") (pintype "input"))
    )
    (net (code "44") (name "SCL") (class "Default")
      (node (ref "OLED128X32") (pin "3") (pinfunction "SCL_3") (pintype "bidirectional"))
      (node (ref "RP1") (pin "1") (pinfunction "1_1") (pintype "passive"))
      (node (ref "U$2") (pin "19/A5") (pinfunction "19/A5/T/SCL0_19/A5") (pintype "bidirectional"))
    )
    (net (code "45") (name "SDA") (class "Default")
      (node (ref "OLED128X32") (pin "4") (pinfunction "SDA_4") (pintype "bidirectional"))
      (node (ref "RP2") (pin "1") (pinfunction "1_1") (pintype "passive"))
      (node (ref "U$2") (pin "18/A4") (pinfunction "18/A4/T/SDA0_18/A4") (pintype "bidirectional"))
    )
    (net (code "46") (name "T1") (class "Default")
      (node (ref "R2") (pin "2") (pinfunction "2_2") (pintype "passive"))
      (node (ref "U$2") (pin "2") (pinfunction "2_2") (pintype "bidirectional"))
    )
    (net (code "47") (name "T2") (class "Default")
      (node (ref "R4") (pin "2") (pinfunction "2_2") (pintype "passive"))
      (node (ref "U$2") (pin "3") (pinfunction "3/CAN-TX/PWM_3") (pintype "bidirectional"))
    )
    (net (code "48") (name "T3") (class "Default")
      (node (ref "R6") (pin "2") (pinfunction "2_2") (pintype "passive"))
      (node (ref "U$2") (pin "4") (pinfunction "4/CAN-RX-PWM_4") (pintype "bidirectional"))
    )
    (net (code "49") (name "T4") (class "Default")
      (node (ref "R8") (pin "2") (pinfunction "2_2") (pintype "passive"))
      (node (ref "U$2") (pin "5") (pinfunction "5/PWM_5") (pintype "bidirectional"))
    )
    (net (code "50") (name "T5") (class "Default")
      (node (ref "R10") (pin "2") (pinfunction "2_2") (pintype "passive"))
      (node (ref "U$2") (pin "6") (pinfunction "6/PWM_6") (pintype "bidirectional"))
    )
    (net (code "51") (name "T6") (class "Default")
      (node (ref "R12") (pin "2") (pinfunction "2_2") (pintype "passive"))
      (node (ref "U$2") (pin "7") (pinfunction "7/RX3_7") (pintype "bidirectional"))
    )
    (net (code "52") (name "T7") (class "Default")
      (node (ref "R14") (pin "2") (pinfunction "2_2") (pintype "passive"))
      (node (ref "U$2") (pin "8") (pinfunction "8/TX3_8") (pintype "bidirectional"))
    )
    (net (code "53") (name "T8") (class "Default")
      (node (ref "R16") (pin "2") (pinfunction "2_2") (pintype "passive"))
      (node (ref "U$2") (pin "9") (pinfunction "9/RX2/PWM_9") (pintype "bidirectional"))
    )
    (net (code "54") (name "T9") (class "Default")
      (node (ref "R18") (pin "2") (pinfunction "2_2") (pintype "passive"))
      (node (ref "U$2") (pin "10") (pinfunction "10/TX2/PWM_10") (pintype "bidirectional"))
    )
    (net (code "55") (name "T10") (class "Default")
      (node (ref "R20") (pin "2") (pinfunction "2_2") (pintype "passive"))
      (node (ref "U$2") (pin "11") (pinfunction "11/MOSI_11") (pintype "bidirectional"))
    )
    (net (code "56") (name "T11") (class "Default")
      (node (ref "R22") (pin "2") (pinfunction "2_2") (pintype "passive"))
      (node (ref "U$2") (pin "12") (pinfunction "12/MISO_12") (pintype "bidirectional"))
    )
    (net (code "57") (name "T12") (class "Default")
      (node (ref "R24") (pin "2") (pinfunction "2_2") (pintype "passive"))
      (node (ref "U$2") (pin "13") (pinfunction "13/SCK/LED_13") (pintype "bidirectional"))
    )
    (net (code "58") (name "TRS_MIDI") (class "Default")
      (node (ref "R30") (pin "2") (pinfunction "2_2") (pintype "passive"))
      (node (ref "U$2") (pin "21/A7") (pinfunction "21/A7/PWM_21/A7") (pintype "bidirectional"))
      (node (ref "U$3") (pin "6") (pinfunction "VO_6") (pintype "passive"))
    )
    (net (code "59") (name "unconnected-(CV-IN-SWITCH-PadP$2_SWITCH)") (class "Default")
      (node (ref "CV-IN") (pin "P$2_SWITCH") (pinfunction "SWITCH_P$2_SWITCH") (pintype "passive"))
    )
    (net (code "60") (name "unconnected-(GI1-SWITCH-PadP$2_SWITCH)") (class "Default")
      (node (ref "GI1") (pin "P$2_SWITCH") (pinfunction "SWITCH_P$2_SWITCH") (pintype "passive"))
    )
    (net (code "61") (name "unconnected-(U$2-0{slash}RX1{slash}T-Pad0)") (class "Default")
      (node (ref "U$2") (pin "0") (pinfunction "0/RX1/T_0") (pintype "bidirectional"))
    )
    (net (code "62") (name "unconnected-(U$2-1{slash}TX1{slash}T-Pad1)") (class "Default")
      (node (ref "U$2") (pin "1") (pinfunction "1/TX1/T_1") (pintype "bidirectional"))
    )
    (net (code "63") (name "unconnected-(U$2-22{slash}A8{slash}T{slash}PWM-Pad22{slash}A8)") (class "Default")
      (node (ref "U$2") (pin "22/A8") (pinfunction "22/A8/T/PWM_22/A8") (pintype "bidirectional"))
    )
    (net (code "64") (name "unconnected-(U$2-23{slash}A9{slash}T{slash}PWM-Pad23{slash}A9)") (class "Default")
      (node (ref "U$2") (pin "23/A9") (pinfunction "23/A9/T/PWM_23/A9") (pintype "bidirectional"))
    )
    (net (code "65") (name "unconnected-(U$2-A14{slash}DAC-PadRESET{slash}DAC)") (class "Default")
      (node (ref "U$2") (pin "RESET/DAC") (pinfunction "A14/DAC_RESET/DAC") (pintype "bidirectional"))
    )
    (net (code "66") (name "unconnected-(U$3-VB-Pad7)") (class "Default")
      (node (ref "U$3") (pin "7") (pinfunction "VB_7") (pintype "passive"))
    )
    (net (code "67") (name "unconnected-(U2-PadNC)") (class "Default")
      (node (ref "U2") (pin "NC") (pinfunction "NC_NC") (pintype "passive"))
    )
  )
)
